# Plate.net
KiCad netlist of a schematic drawn in Altium Designer
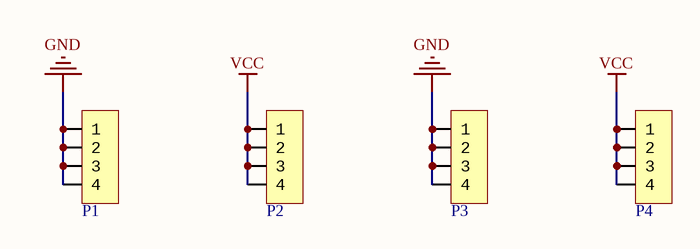
[diagram p0: Plate.SchDoc]

(export (version "E")
  (design (tool "Eeschema 10.0.6"))
  (components
    (comp (ref "P1")
      (value "HDR1x4_2.54")
      (footprint "HDR_1X4")
      (description "Header")
      (libsource (lib "Beacon") (part "HDR1x4_2.54"))
    )
    (comp (ref "P2")
      (value "HDR1x4_2.54")
      (footprint "HDR_1X4")
      (description "Header")
      (libsource (lib "Beacon") (part "HDR1x4_2.54"))
    )
    (comp (ref "P3")
      (value "HDR1x4_2.54")
      (footprint "HDR_1X4")
      (description "Header")
      (libsource (lib "Beacon") (part "HDR1x4_2.54"))
    )
    (comp (ref "P4")
      (value "HDR1x4_2.54")
      (footprint "HDR_1X4")
      (description "Header")
      (libsource (lib "Beacon") (part "HDR1x4_2.54"))
    )
  )
  (nets
    (net (code "1") (name "GND") (class "Default")
      (node (ref "P1") (pin "1") (pinfunction "1_1") (pintype "passive"))
      (node (ref "P1") (pin "2") (pinfunction "2_2") (pintype "passive"))
      (node (ref "P1") (pin "3") (pinfunction "3_3") (pintype "passive"))
      (node (ref "P1") (pin "4") (pinfunction "4_4") (pintype "passive"))
      (node (ref "P3") (pin "1") (pinfunction "1_1") (pintype "passive"))
      (node (ref "P3") (pin "2") (pinfunction "2_2") (pintype "passive"))
      (node (ref "P3") (pin "3") (pinfunction "3_3") (pintype "passive"))
      (node (ref "P3") (pin "4") (pinfunction "4_4") (pintype "passive"))
    )
    (net (code "2") (name "VCC") (class "Default")
      (node (ref "P2") (pin "1") (pinfunction "1_1") (pintype "passive"))
      (node (ref "P2") (pin "2") (pinfunction "2_2") (pintype "passive"))
      (node (ref "P2") (pin "3") (pinfunction "3_3") (pintype "passive"))
      (node (ref "P2") (pin "4") (pinfunction "4_4") (pintype "passive"))
      (node (ref "P4") (pin "1") (pinfunction "1_1") (pintype "passive"))
      (node (ref "P4") (pin "2") (pinfunction "2_2") (pintype "passive"))
      (node (ref "P4") (pin "3") (pinfunction "3_3") (pintype "passive"))
      (node (ref "P4") (pin "4") (pinfunction "4_4") (pintype "passive"))
    )
  )
)
